# Light_Sensor.net
KiCad netlist of a schematic drawn in EAGLE
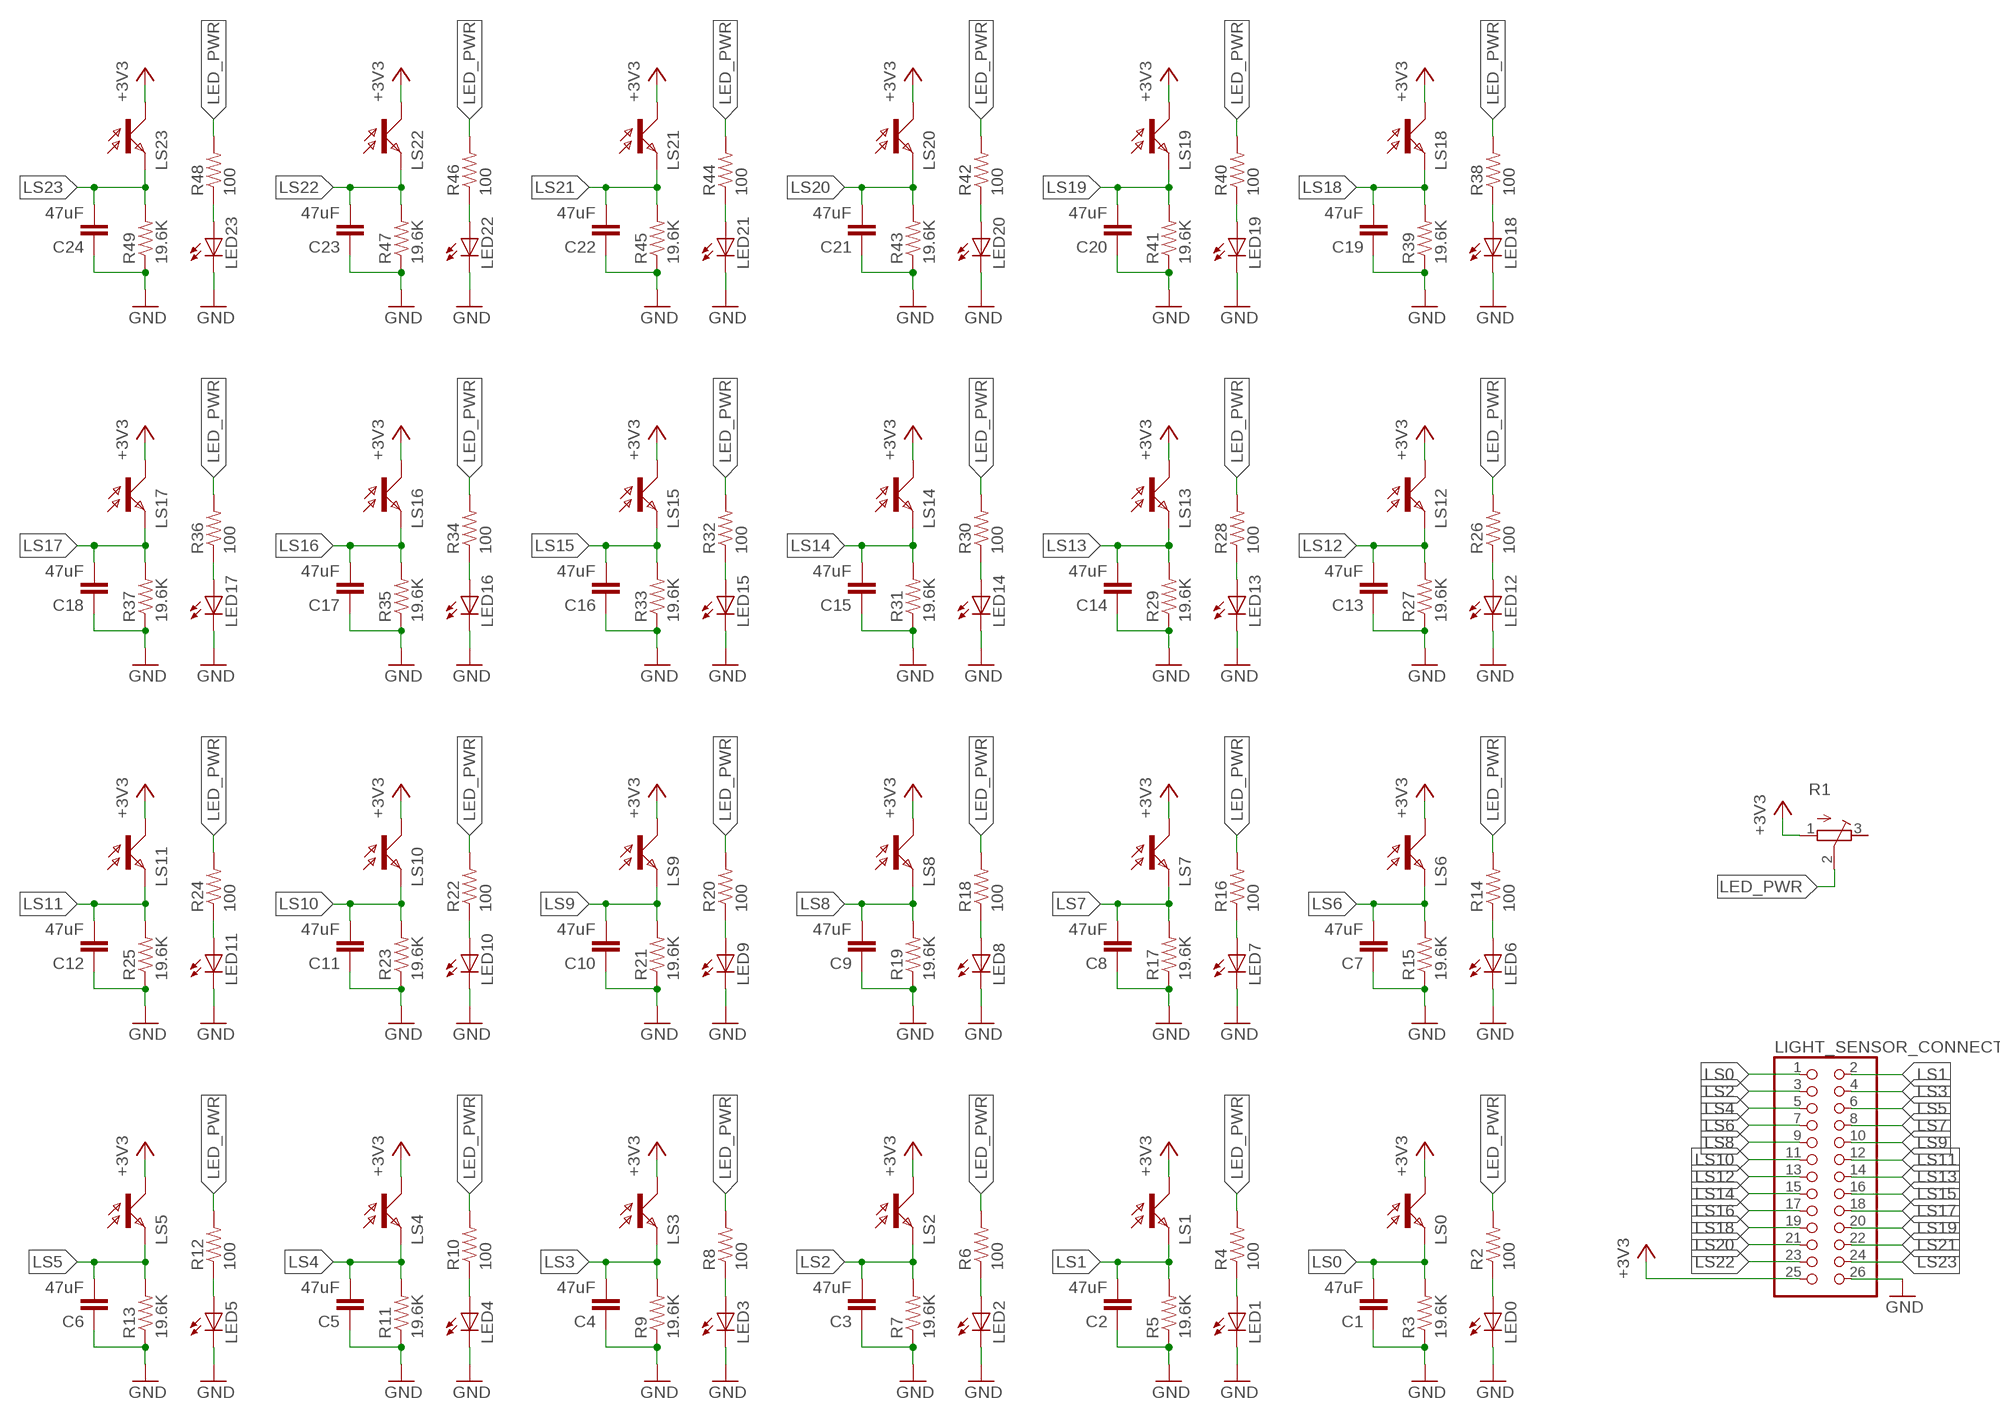
[diagram p0: schematic, sheet 1]

(export (version "E")
  (design (tool "Eeschema 10.0.6"))
  (components
    (comp (ref "C1")
      (value "47uF")
      (footprint "eagle-import:1206")
      (libsource (lib "eagle-import") (part "CAP1206"))
    )
    (comp (ref "C2")
      (value "47uF")
      (footprint "eagle-import:1206")
      (libsource (lib "eagle-import") (part "CAP1206"))
    )
    (comp (ref "C3")
      (value "47uF")
      (footprint "eagle-import:1206")
      (libsource (lib "eagle-import") (part "CAP1206"))
    )
    (comp (ref "C4")
      (value "47uF")
      (footprint "eagle-import:1206")
      (libsource (lib "eagle-import") (part "CAP1206"))
    )
    (comp (ref "C5")
      (value "47uF")
      (footprint "eagle-import:1206")
      (libsource (lib "eagle-import") (part "CAP1206"))
    )
    (comp (ref "C6")
      (value "47uF")
      (footprint "eagle-import:1206")
      (libsource (lib "eagle-import") (part "CAP1206"))
    )
    (comp (ref "C7")
      (value "47uF")
      (footprint "eagle-import:1206")
      (libsource (lib "eagle-import") (part "CAP1206"))
    )
    (comp (ref "C8")
      (value "47uF")
      (footprint "eagle-import:1206")
      (libsource (lib "eagle-import") (part "CAP1206"))
    )
    (comp (ref "C9")
      (value "47uF")
      (footprint "eagle-import:1206")
      (libsource (lib "eagle-import") (part "CAP1206"))
    )
    (comp (ref "C10")
      (value "47uF")
      (footprint "eagle-import:1206")
      (libsource (lib "eagle-import") (part "CAP1206"))
    )
    (comp (ref "C11")
      (value "47uF")
      (footprint "eagle-import:1206")
      (libsource (lib "eagle-import") (part "CAP1206"))
    )
    (comp (ref "C12")
      (value "47uF")
      (footprint "eagle-import:1206")
      (libsource (lib "eagle-import") (part "CAP1206"))
    )
    (comp (ref "C13")
      (value "47uF")
      (footprint "eagle-import:1206")
      (libsource (lib "eagle-import") (part "CAP1206"))
    )
    (comp (ref "C14")
      (value "47uF")
      (footprint "eagle-import:1206")
      (libsource (lib "eagle-import") (part "CAP1206"))
    )
    (comp (ref "C15")
      (value "47uF")
      (footprint "eagle-import:1206")
      (libsource (lib "eagle-import") (part "CAP1206"))
    )
    (comp (ref "C16")
      (value "47uF")
      (footprint "eagle-import:1206")
      (libsource (lib "eagle-import") (part "CAP1206"))
    )
    (comp (ref "C17")
      (value "47uF")
      (footprint "eagle-import:1206")
      (libsource (lib "eagle-import") (part "CAP1206"))
    )
    (comp (ref "C18")
      (value "47uF")
      (footprint "eagle-import:1206")
      (libsource (lib "eagle-import") (part "CAP1206"))
    )
    (comp (ref "C19")
      (value "47uF")
      (footprint "eagle-import:1206")
      (libsource (lib "eagle-import") (part "CAP1206"))
    )
    (comp (ref "C20")
      (value "47uF")
      (footprint "eagle-import:1206")
      (libsource (lib "eagle-import") (part "CAP1206"))
    )
    (comp (ref "C21")
      (value "47uF")
      (footprint "eagle-import:1206")
      (libsource (lib "eagle-import") (part "CAP1206"))
    )
    (comp (ref "C22")
      (value "47uF")
      (footprint "eagle-import:1206")
      (libsource (lib "eagle-import") (part "CAP1206"))
    )
    (comp (ref "C23")
      (value "47uF")
      (footprint "eagle-import:1206")
      (libsource (lib "eagle-import") (part "CAP1206"))
    )
    (comp (ref "C24")
      (value "47uF")
      (footprint "eagle-import:1206")
      (libsource (lib "eagle-import") (part "CAP1206"))
    )
    (comp (ref "LED0")
      (value "LEDCHIP-LED0603")
      (footprint "eagle-import:CHIP-LED0603")
      (libsource (lib "eagle-import") (part "LEDCHIP-LED0603"))
    )
    (comp (ref "LED1")
      (value "LEDCHIP-LED0603")
      (footprint "eagle-import:CHIP-LED0603")
      (libsource (lib "eagle-import") (part "LEDCHIP-LED0603"))
    )
    (comp (ref "LED2")
      (value "LEDCHIP-LED0603")
      (footprint "eagle-import:CHIP-LED0603")
      (libsource (lib "eagle-import") (part "LEDCHIP-LED0603"))
    )
    (comp (ref "LED3")
      (value "LEDCHIP-LED0603")
      (footprint "eagle-import:CHIP-LED0603")
      (libsource (lib "eagle-import") (part "LEDCHIP-LED0603"))
    )
    (comp (ref "LED4")
      (value "LEDCHIP-LED0603")
      (footprint "eagle-import:CHIP-LED0603")
      (libsource (lib "eagle-import") (part "LEDCHIP-LED0603"))
    )
    (comp (ref "LED5")
      (value "LEDCHIP-LED0603")
      (footprint "eagle-import:CHIP-LED0603")
      (libsource (lib "eagle-import") (part "LEDCHIP-LED0603"))
    )
    (comp (ref "LED6")
      (value "LEDCHIP-LED0603")
      (footprint "eagle-import:CHIP-LED0603")
      (libsource (lib "eagle-import") (part "LEDCHIP-LED0603"))
    )
    (comp (ref "LED7")
      (value "LEDCHIP-LED0603")
      (footprint "eagle-import:CHIP-LED0603")
      (libsource (lib "eagle-import") (part "LEDCHIP-LED0603"))
    )
    (comp (ref "LED8")
      (value "LEDCHIP-LED0603")
      (footprint "eagle-import:CHIP-LED0603")
      (libsource (lib "eagle-import") (part "LEDCHIP-LED0603"))
    )
    (comp (ref "LED9")
      (value "LEDCHIP-LED0603")
      (footprint "eagle-import:CHIP-LED0603")
      (libsource (lib "eagle-import") (part "LEDCHIP-LED0603"))
    )
    (comp (ref "LED10")
      (value "LEDCHIP-LED0603")
      (footprint "eagle-import:CHIP-LED0603")
      (libsource (lib "eagle-import") (part "LEDCHIP-LED0603"))
    )
    (comp (ref "LED11")
      (value "LEDCHIP-LED0603")
      (footprint "eagle-import:CHIP-LED0603")
      (libsource (lib "eagle-import") (part "LEDCHIP-LED0603"))
    )
    (comp (ref "LED12")
      (value "LEDCHIP-LED0603")
      (footprint "eagle-import:CHIP-LED0603")
      (libsource (lib "eagle-import") (part "LEDCHIP-LED0603"))
    )
    (comp (ref "LED13")
      (value "LEDCHIP-LED0603")
      (footprint "eagle-import:CHIP-LED0603")
      (libsource (lib "eagle-import") (part "LEDCHIP-LED0603"))
    )
    (comp (ref "LED14")
      (value "LEDCHIP-LED0603")
      (footprint "eagle-import:CHIP-LED0603")
      (libsource (lib "eagle-import") (part "LEDCHIP-LED0603"))
    )
    (comp (ref "LED15")
      (value "LEDCHIP-LED0603")
      (footprint "eagle-import:CHIP-LED0603")
      (libsource (lib "eagle-import") (part "LEDCHIP-LED0603"))
    )
    (comp (ref "LED16")
      (value "LEDCHIP-LED0603")
      (footprint "eagle-import:CHIP-LED0603")
      (libsource (lib "eagle-import") (part "LEDCHIP-LED0603"))
    )
    (comp (ref "LED17")
      (value "LEDCHIP-LED0603")
      (footprint "eagle-import:CHIP-LED0603")
      (libsource (lib "eagle-import") (part "LEDCHIP-LED0603"))
    )
    (comp (ref "LED18")
      (value "LEDCHIP-LED0603")
      (footprint "eagle-import:CHIP-LED0603")
      (libsource (lib "eagle-import") (part "LEDCHIP-LED0603"))
    )
    (comp (ref "LED19")
      (value "LEDCHIP-LED0603")
      (footprint "eagle-import:CHIP-LED0603")
      (libsource (lib "eagle-import") (part "LEDCHIP-LED0603"))
    )
    (comp (ref "LED20")
      (value "LEDCHIP-LED0603")
      (footprint "eagle-import:CHIP-LED0603")
      (libsource (lib "eagle-import") (part "LEDCHIP-LED0603"))
    )
    (comp (ref "LED21")
      (value "LEDCHIP-LED0603")
      (footprint "eagle-import:CHIP-LED0603")
      (libsource (lib "eagle-import") (part "LEDCHIP-LED0603"))
    )
    (comp (ref "LED22")
      (value "LEDCHIP-LED0603")
      (footprint "eagle-import:CHIP-LED0603")
      (libsource (lib "eagle-import") (part "LEDCHIP-LED0603"))
    )
    (comp (ref "LED23")
      (value "LEDCHIP-LED0603")
      (footprint "eagle-import:CHIP-LED0603")
      (libsource (lib "eagle-import") (part "LEDCHIP-LED0603"))
    )
    (comp (ref "LIGHT_SENSOR_CONNECTOR")
      (value "PINHD-2X13SMT")
      (footprint "eagle-import:2X13_SMT")
      (libsource (lib "eagle-import") (part "PINHD-2X13SMT"))
    )
    (comp (ref "LS0")
      (value "ALS")
      (footprint "eagle-import:SMD")
      (libsource (lib "eagle-import") (part "ALS"))
    )
    (comp (ref "LS1")
      (value "ALS")
      (footprint "eagle-import:SMD")
      (libsource (lib "eagle-import") (part "ALS"))
    )
    (comp (ref "LS2")
      (value "ALS")
      (footprint "eagle-import:SMD")
      (libsource (lib "eagle-import") (part "ALS"))
    )
    (comp (ref "LS3")
      (value "ALS")
      (footprint "eagle-import:SMD")
      (libsource (lib "eagle-import") (part "ALS"))
    )
    (comp (ref "LS4")
      (value "ALS")
      (footprint "eagle-import:SMD")
      (libsource (lib "eagle-import") (part "ALS"))
    )
    (comp (ref "LS5")
      (value "ALS")
      (footprint "eagle-import:SMD")
      (libsource (lib "eagle-import") (part "ALS"))
    )
    (comp (ref "LS6")
      (value "ALS")
      (footprint "eagle-import:SMD")
      (libsource (lib "eagle-import") (part "ALS"))
    )
    (comp (ref "LS7")
      (value "ALS")
      (footprint "eagle-import:SMD")
      (libsource (lib "eagle-import") (part "ALS"))
    )
    (comp (ref "LS8")
      (value "ALS")
      (footprint "eagle-import:SMD")
      (libsource (lib "eagle-import") (part "ALS"))
    )
    (comp (ref "LS9")
      (value "ALS")
      (footprint "eagle-import:SMD")
      (libsource (lib "eagle-import") (part "ALS"))
    )
    (comp (ref "LS10")
      (value "ALS")
      (footprint "eagle-import:SMD")
      (libsource (lib "eagle-import") (part "ALS"))
    )
    (comp (ref "LS11")
      (value "ALS")
      (footprint "eagle-import:SMD")
      (libsource (lib "eagle-import") (part "ALS"))
    )
    (comp (ref "LS12")
      (value "ALS")
      (footprint "eagle-import:SMD")
      (libsource (lib "eagle-import") (part "ALS"))
    )
    (comp (ref "LS13")
      (value "ALS")
      (footprint "eagle-import:SMD")
      (libsource (lib "eagle-import") (part "ALS"))
    )
    (comp (ref "LS14")
      (value "ALS")
      (footprint "eagle-import:SMD")
      (libsource (lib "eagle-import") (part "ALS"))
    )
    (comp (ref "LS15")
      (value "ALS")
      (footprint "eagle-import:SMD")
      (libsource (lib "eagle-import") (part "ALS"))
    )
    (comp (ref "LS16")
      (value "ALS")
      (footprint "eagle-import:SMD")
      (libsource (lib "eagle-import") (part "ALS"))
    )
    (comp (ref "LS17")
      (value "ALS")
      (footprint "eagle-import:SMD")
      (libsource (lib "eagle-import") (part "ALS"))
    )
    (comp (ref "LS18")
      (value "ALS")
      (footprint "eagle-import:SMD")
      (libsource (lib "eagle-import") (part "ALS"))
    )
    (comp (ref "LS19")
      (value "ALS")
      (footprint "eagle-import:SMD")
      (libsource (lib "eagle-import") (part "ALS"))
    )
    (comp (ref "LS20")
      (value "ALS")
      (footprint "eagle-import:SMD")
      (libsource (lib "eagle-import") (part "ALS"))
    )
    (comp (ref "LS21")
      (value "ALS")
      (footprint "eagle-import:SMD")
      (libsource (lib "eagle-import") (part "ALS"))
    )
    (comp (ref "LS22")
      (value "ALS")
      (footprint "eagle-import:SMD")
      (libsource (lib "eagle-import") (part "ALS"))
    )
    (comp (ref "LS23")
      (value "ALS")
      (footprint "eagle-import:SMD")
      (libsource (lib "eagle-import") (part "ALS"))
    )
    (comp (ref "R1")
      (value "R-TRIMM3296W")
      (footprint "eagle-import:RTRIM3296W")
      (libsource (lib "eagle-import") (part "R-TRIMM3296W"))
    )
    (comp (ref "R2")
      (value "100")
      (footprint "eagle-import:0603-RES")
      (libsource (lib "eagle-import") (part "RESISTOR0603"))
    )
    (comp (ref "R3")
      (value "19.6K")
      (footprint "eagle-import:0603-RES")
      (libsource (lib "eagle-import") (part "RESISTOR0603"))
    )
    (comp (ref "R4")
      (value "100")
      (footprint "eagle-import:0603-RES")
      (libsource (lib "eagle-import") (part "RESISTOR0603"))
    )
    (comp (ref "R5")
      (value "19.6K")
      (footprint "eagle-import:0603-RES")
      (libsource (lib "eagle-import") (part "RESISTOR0603"))
    )
    (comp (ref "R6")
      (value "100")
      (footprint "eagle-import:0603-RES")
      (libsource (lib "eagle-import") (part "RESISTOR0603"))
    )
    (comp (ref "R7")
      (value "19.6K")
      (footprint "eagle-import:0603-RES")
      (libsource (lib "eagle-import") (part "RESISTOR0603"))
    )
    (comp (ref "R8")
      (value "100")
      (footprint "eagle-import:0603-RES")
      (libsource (lib "eagle-import") (part "RESISTOR0603"))
    )
    (comp (ref "R9")
      (value "19.6K")
      (footprint "eagle-import:0603-RES")
      (libsource (lib "eagle-import") (part "RESISTOR0603"))
    )
    (comp (ref "R10")
      (value "100")
      (footprint "eagle-import:0603-RES")
      (libsource (lib "eagle-import") (part "RESISTOR0603"))
    )
    (comp (ref "R11")
      (value "19.6K")
      (footprint "eagle-import:0603-RES")
      (libsource (lib "eagle-import") (part "RESISTOR0603"))
    )
    (comp (ref "R12")
      (value "100")
      (footprint "eagle-import:0603-RES")
      (libsource (lib "eagle-import") (part "RESISTOR0603"))
    )
    (comp (ref "R13")
      (value "19.6K")
      (footprint "eagle-import:0603-RES")
      (libsource (lib "eagle-import") (part "RESISTOR0603"))
    )
    (comp (ref "R14")
      (value "100")
      (footprint "eagle-import:0603-RES")
      (libsource (lib "eagle-import") (part "RESISTOR0603"))
    )
    (comp (ref "R15")
      (value "19.6K")
      (footprint "eagle-import:0603-RES")
      (libsource (lib "eagle-import") (part "RESISTOR0603"))
    )
    (comp (ref "R16")
      (value "100")
      (footprint "eagle-import:0603-RES")
      (libsource (lib "eagle-import") (part "RESISTOR0603"))
    )
    (comp (ref "R17")
      (value "19.6K")
      (footprint "eagle-import:0603-RES")
      (libsource (lib "eagle-import") (part "RESISTOR0603"))
    )
    (comp (ref "R18")
      (value "100")
      (footprint "eagle-import:0603-RES")
      (libsource (lib "eagle-import") (part "RESISTOR0603"))
    )
    (comp (ref "R19")
      (value "19.6K")
      (footprint "eagle-import:0603-RES")
      (libsource (lib "eagle-import") (part "RESISTOR0603"))
    )
    (comp (ref "R20")
      (value "100")
      (footprint "eagle-import:0603-RES")
      (libsource (lib "eagle-import") (part "RESISTOR0603"))
    )
    (comp (ref "R21")
      (value "19.6K")
      (footprint "eagle-import:0603-RES")
      (libsource (lib "eagle-import") (part "RESISTOR0603"))
    )
    (comp (ref "R22")
      (value "100")
      (footprint "eagle-import:0603-RES")
      (libsource (lib "eagle-import") (part "RESISTOR0603"))
    )
    (comp (ref "R23")
      (value "19.6K")
      (footprint "eagle-import:0603-RES")
      (libsource (lib "eagle-import") (part "RESISTOR0603"))
    )
    (comp (ref "R24")
      (value "100")
      (footprint "eagle-import:0603-RES")
      (libsource (lib "eagle-import") (part "RESISTOR0603"))
    )
    (comp (ref "R25")
      (value "19.6K")
      (footprint "eagle-import:0603-RES")
      (libsource (lib "eagle-import") (part "RESISTOR0603"))
    )
    (comp (ref "R26")
      (value "100")
      (footprint "eagle-import:0603-RES")
      (libsource (lib "eagle-import") (part "RESISTOR0603"))
    )
    (comp (ref "R27")
      (value "19.6K")
      (footprint "eagle-import:0603-RES")
      (libsource (lib "eagle-import") (part "RESISTOR0603"))
    )
    (comp (ref "R28")
      (value "100")
      (footprint "eagle-import:0603-RES")
      (libsource (lib "eagle-import") (part "RESISTOR0603"))
    )
    (comp (ref "R29")
      (value "19.6K")
      (footprint "eagle-import:0603-RES")
      (libsource (lib "eagle-import") (part "RESISTOR0603"))
    )
    (comp (ref "R30")
      (value "100")
      (footprint "eagle-import:0603-RES")
      (libsource (lib "eagle-import") (part "RESISTOR0603"))
    )
    (comp (ref "R31")
      (value "19.6K")
      (footprint "eagle-import:0603-RES")
      (libsource (lib "eagle-import") (part "RESISTOR0603"))
    )
    (comp (ref "R32")
      (value "100")
      (footprint "eagle-import:0603-RES")
      (libsource (lib "eagle-import") (part "RESISTOR0603"))
    )
    (comp (ref "R33")
      (value "19.6K")
      (footprint "eagle-import:0603-RES")
      (libsource (lib "eagle-import") (part "RESISTOR0603"))
    )
    (comp (ref "R34")
      (value "100")
      (footprint "eagle-import:0603-RES")
      (libsource (lib "eagle-import") (part "RESISTOR0603"))
    )
    (comp (ref "R35")
      (value "19.6K")
      (footprint "eagle-import:0603-RES")
      (libsource (lib "eagle-import") (part "RESISTOR0603"))
    )
    (comp (ref "R36")
      (value "100")
      (footprint "eagle-import:0603-RES")
      (libsource (lib "eagle-import") (part "RESISTOR0603"))
    )
    (comp (ref "R37")
      (value "19.6K")
      (footprint "eagle-import:0603-RES")
      (libsource (lib "eagle-import") (part "RESISTOR0603"))
    )
    (comp (ref "R38")
      (value "100")
      (footprint "eagle-import:0603-RES")
      (libsource (lib "eagle-import") (part "RESISTOR0603"))
    )
    (comp (ref "R39")
      (value "19.6K")
      (footprint "eagle-import:0603-RES")
      (libsource (lib "eagle-import") (part "RESISTOR0603"))
    )
    (comp (ref "R40")
      (value "100")
      (footprint "eagle-import:0603-RES")
      (libsource (lib "eagle-import") (part "RESISTOR0603"))
    )
    (comp (ref "R41")
      (value "19.6K")
      (footprint "eagle-import:0603-RES")
      (libsource (lib "eagle-import") (part "RESISTOR0603"))
    )
    (comp (ref "R42")
      (value "100")
      (footprint "eagle-import:0603-RES")
      (libsource (lib "eagle-import") (part "RESISTOR0603"))
    )
    (comp (ref "R43")
      (value "19.6K")
      (footprint "eagle-import:0603-RES")
      (libsource (lib "eagle-import") (part "RESISTOR0603"))
    )
    (comp (ref "R44")
      (value "100")
      (footprint "eagle-import:0603-RES")
      (libsource (lib "eagle-import") (part "RESISTOR0603"))
    )
    (comp (ref "R45")
      (value "19.6K")
      (footprint "eagle-import:0603-RES")
      (libsource (lib "eagle-import") (part "RESISTOR0603"))
    )
    (comp (ref "R46")
      (value "100")
      (footprint "eagle-import:0603-RES")
      (libsource (lib "eagle-import") (part "RESISTOR0603"))
    )
    (comp (ref "R47")
      (value "19.6K")
      (footprint "eagle-import:0603-RES")
      (libsource (lib "eagle-import") (part "RESISTOR0603"))
    )
    (comp (ref "R48")
      (value "100")
      (footprint "eagle-import:0603-RES")
      (libsource (lib "eagle-import") (part "RESISTOR0603"))
    )
    (comp (ref "R49")
      (value "19.6K")
      (footprint "eagle-import:0603-RES")
      (libsource (lib "eagle-import") (part "RESISTOR0603"))
    )
  )
  (nets
    (net (code "1") (name "+3V3") (class "Default")
      (node (ref "LIGHT_SENSOR_CONNECTOR") (pin "25") (pinfunction "25_25") (pintype "passive"))
      (node (ref "LS0") (pin "C") (pinfunction "C_C") (pintype "passive"))
      (node (ref "LS1") (pin "C") (pinfunction "C_C") (pintype "passive"))
      (node (ref "LS10") (pin "C") (pinfunction "C_C") (pintype "passive"))
      (node (ref "LS11") (pin "C") (pinfunction "C_C") (pintype "passive"))
      (node (ref "LS12") (pin "C") (pinfunction "C_C") (pintype "passive"))
      (node (ref "LS13") (pin "C") (pinfunction "C_C") (pintype "passive"))
      (node (ref "LS14") (pin "C") (pinfunction "C_C") (pintype "passive"))
      (node (ref "LS15") (pin "C") (pinfunction "C_C") (pintype "passive"))
      (node (ref "LS16") (pin "C") (pinfunction "C_C") (pintype "passive"))
      (node (ref "LS17") (pin "C") (pinfunction "C_C") (pintype "passive"))
      (node (ref "LS18") (pin "C") (pinfunction "C_C") (pintype "passive"))
      (node (ref "LS19") (pin "C") (pinfunction "C_C") (pintype "passive"))
      (node (ref "LS2") (pin "C") (pinfunction "C_C") (pintype "passive"))
      (node (ref "LS20") (pin "C") (pinfunction "C_C") (pintype "passive"))
      (node (ref "LS21") (pin "C") (pinfunction "C_C") (pintype "passive"))
      (node (ref "LS22") (pin "C") (pinfunction "C_C") (pintype "passive"))
      (node (ref "LS23") (pin "C") (pinfunction "C_C") (pintype "passive"))
      (node (ref "LS3") (pin "C") (pinfunction "C_C") (pintype "passive"))
      (node (ref "LS4") (pin "C") (pinfunction "C_C") (pintype "passive"))
      (node (ref "LS5") (pin "C") (pinfunction "C_C") (pintype "passive"))
      (node (ref "LS6") (pin "C") (pinfunction "C_C") (pintype "passive"))
      (node (ref "LS7") (pin "C") (pinfunction "C_C") (pintype "passive"))
      (node (ref "LS8") (pin "C") (pinfunction "C_C") (pintype "passive"))
      (node (ref "LS9") (pin "C") (pinfunction "C_C") (pintype "passive"))
      (node (ref "R1") (pin "1") (pinfunction "A_1") (pintype "passive"))
    )
    (net (code "2") (name "GND") (class "Default")
      (node (ref "C1") (pin "1") (pinfunction "1_1") (pintype "passive"))
      (node (ref "C10") (pin "1") (pinfunction "1_1") (pintype "passive"))
      (node (ref "C11") (pin "1") (pinfunction "1_1") (pintype "passive"))
      (node (ref "C12") (pin "1") (pinfunction "1_1") (pintype "passive"))
      (node (ref "C13") (pin "1") (pinfunction "1_1") (pintype "passive"))
      (node (ref "C14") (pin "1") (pinfunction "1_1") (pintype "passive"))
      (node (ref "C15") (pin "1") (pinfunction "1_1") (pintype "passive"))
      (node (ref "C16") (pin "1") (pinfunction "1_1") (pintype "passive"))
      (node (ref "C17") (pin "1") (pinfunction "1_1") (pintype "passive"))
      (node (ref "C18") (pin "1") (pinfunction "1_1") (pintype "passive"))
      (node (ref "C19") (pin "1") (pinfunction "1_1") (pintype "passive"))
      (node (ref "C2") (pin "1") (pinfunction "1_1") (pintype "passive"))
      (node (ref "C20") (pin "1") (pinfunction "1_1") (pintype "passive"))
      (node (ref "C21") (pin "1") (pinfunction "1_1") (pintype "passive"))
      (node (ref "C22") (pin "1") (pinfunction "1_1") (pintype "passive"))
      (node (ref "C23") (pin "1") (pinfunction "1_1") (pintype "passive"))
      (node (ref "C24") (pin "1") (pinfunction "1_1") (pintype "passive"))
      (node (ref "C3") (pin "1") (pinfunction "1_1") (pintype "passive"))
      (node (ref "C4") (pin "1") (pinfunction "1_1") (pintype "passive"))
      (node (ref "C5") (pin "1") (pinfunction "1_1") (pintype "passive"))
      (node (ref "C6") (pin "1") (pinfunction "1_1") (pintype "passive"))
      (node (ref "C7") (pin "1") (pinfunction "1_1") (pintype "passive"))
      (node (ref "C8") (pin "1") (pinfunction "1_1") (pintype "passive"))
      (node (ref "C9") (pin "1") (pinfunction "1_1") (pintype "passive"))
      (node (ref "LED0") (pin "C") (pinfunction "C_C") (pintype "passive"))
      (node (ref "LED1") (pin "C") (pinfunction "C_C") (pintype "passive"))
      (node (ref "LED10") (pin "C") (pinfunction "C_C") (pintype "passive"))
      (node (ref "LED11") (pin "C") (pinfunction "C_C") (pintype "passive"))
      (node (ref "LED12") (pin "C") (pinfunction "C_C") (pintype "passive"))
      (node (ref "LED13") (pin "C") (pinfunction "C_C") (pintype "passive"))
      (node (ref "LED14") (pin "C") (pinfunction "C_C") (pintype "passive"))
      (node (ref "LED15") (pin "C") (pinfunction "C_C") (pintype "passive"))
      (node (ref "LED16") (pin "C") (pinfunction "C_C") (pintype "passive"))
      (node (ref "LED17") (pin "C") (pinfunction "C_C") (pintype "passive"))
      (node (ref "LED18") (pin "C") (pinfunction "C_C") (pintype "passive"))
      (node (ref "LED19") (pin "C") (pinfunction "C_C") (pintype "passive"))
      (node (ref "LED2") (pin "C") (pinfunction "C_C") (pintype "passive"))
      (node (ref "LED20") (pin "C") (pinfunction "C_C") (pintype "passive"))
      (node (ref "LED21") (pin "C") (pinfunction "C_C") (pintype "passive"))
      (node (ref "LED22") (pin "C") (pinfunction "C_C") (pintype "passive"))
      (node (ref "LED23") (pin "C") (pinfunction "C_C") (pintype "passive"))
      (node (ref "LED3") (pin "C") (pinfunction "C_C") (pintype "passive"))
      (node (ref "LED4") (pin "C") (pinfunction "C_C") (pintype "passive"))
      (node (ref "LED5") (pin "C") (pinfunction "C_C") (pintype "passive"))
      (node (ref "LED6") (pin "C") (pinfunction "C_C") (pintype "passive"))
      (node (ref "LED7") (pin "C") (pinfunction "C_C") (pintype "passive"))
      (node (ref "LED8") (pin "C") (pinfunction "C_C") (pintype "passive"))
      (node (ref "LED9") (pin "C") (pinfunction "C_C") (pintype "passive"))
      (node (ref "LIGHT_SENSOR_CONNECTOR") (pin "26") (pinfunction "26_26") (pintype "passive"))
      (node (ref "R11") (pin "1") (pinfunction "1_1") (pintype "passive"))
      (node (ref "R13") (pin "1") (pinfunction "1_1") (pintype "passive"))
      (node (ref "R15") (pin "1") (pinfunction "1_1") (pintype "passive"))
      (node (ref "R17") (pin "1") (pinfunction "1_1") (pintype "passive"))
      (node (ref "R19") (pin "1") (pinfunction "1_1") (pintype "passive"))
      (node (ref "R21") (pin "1") (pinfunction "1_1") (pintype "passive"))
      (node (ref "R23") (pin "1") (pinfunction "1_1") (pintype "passive"))
      (node (ref "R25") (pin "1") (pinfunction "1_1") (pintype "passive"))
      (node (ref "R27") (pin "1") (pinfunction "1_1") (pintype "passive"))
      (node (ref "R29") (pin "1") (pinfunction "1_1") (pintype "passive"))
      (node (ref "R3") (pin "1") (pinfunction "1_1") (pintype "passive"))
      (node (ref "R31") (pin "1") (pinfunction "1_1") (pintype "passive"))
      (node (ref "R33") (pin "1") (pinfunction "1_1") (pintype "passive"))
      (node (ref "R35") (pin "1") (pinfunction "1_1") (pintype "passive"))
      (node (ref "R37") (pin "1") (pinfunction "1_1") (pintype "passive"))
      (node (ref "R39") (pin "1") (pinfunction "1_1") (pintype "passive"))
      (node (ref "R41") (pin "1") (pinfunction "1_1") (pintype "passive"))
      (node (ref "R43") (pin "1") (pinfunction "1_1") (pintype "passive"))
      (node (ref "R45") (pin "1") (pinfunction "1_1") (pintype "passive"))
      (node (ref "R47") (pin "1") (pinfunction "1_1") (pintype "passive"))
      (node (ref "R49") (pin "1") (pinfunction "1_1") (pintype "passive"))
      (node (ref "R5") (pin "1") (pinfunction "1_1") (pintype "passive"))
      (node (ref "R7") (pin "1") (pinfunction "1_1") (pintype "passive"))
      (node (ref "R9") (pin "1") (pinfunction "1_1") (pintype "passive"))
    )
    (net (code "3") (name "LED_PWR") (class "Default")
      (node (ref "R1") (pin "2") (pinfunction "S_2") (pintype "passive"))
      (node (ref "R10") (pin "2") (pinfunction "2_2") (pintype "passive"))
      (node (ref "R12") (pin "2") (pinfunction "2_2") (pintype "passive"))
      (node (ref "R14") (pin "2") (pinfunction "2_2") (pintype "passive"))
      (node (ref "R16") (pin "2") (pinfunction "2_2") (pintype "passive"))
      (node (ref "R18") (pin "2") (pinfunction "2_2") (pintype "passive"))
      (node (ref "R2") (pin "2") (pinfunction "2_2") (pintype "passive"))
      (node (ref "R20") (pin "2") (pinfunction "2_2") (pintype "passive"))
      (node (ref "R22") (pin "2") (pinfunction "2_2") (pintype "passive"))
      (node (ref "R24") (pin "2") (pinfunction "2_2") (pintype "passive"))
      (node (ref "R26") (pin "2") (pinfunction "2_2") (pintype "passive"))
      (node (ref "R28") (pin "2") (pinfunction "2_2") (pintype "passive"))
      (node (ref "R30") (pin "2") (pinfunction "2_2") (pintype "passive"))
      (node (ref "R32") (pin "2") (pinfunction "2_2") (pintype "passive"))
      (node (ref "R34") (pin "2") (pinfunction "2_2") (pintype "passive"))
      (node (ref "R36") (pin "2") (pinfunction "2_2") (pintype "passive"))
      (node (ref "R38") (pin "2") (pinfunction "2_2") (pintype "passive"))
      (node (ref "R4") (pin "2") (pinfunction "2_2") (pintype "passive"))
      (node (ref "R40") (pin "2") (pinfunction "2_2") (pintype "passive"))
      (node (ref "R42") (pin "2") (pinfunction "2_2") (pintype "passive"))
      (node (ref "R44") (pin "2") (pinfunction "2_2") (pintype "passive"))
      (node (ref "R46") (pin "2") (pinfunction "2_2") (pintype "passive"))
      (node (ref "R48") (pin "2") (pinfunction "2_2") (pintype "passive"))
      (node (ref "R6") (pin "2") (pinfunction "2_2") (pintype "passive"))
      (node (ref "R8") (pin "2") (pinfunction "2_2") (pintype "passive"))
    )
    (net (code "4") (name "LS0") (class "Default")
      (node (ref "C1") (pin "2") (pinfunction "2_2") (pintype "passive"))
      (node (ref "LIGHT_SENSOR_CONNECTOR") (pin "1") (pinfunction "1_1") (pintype "passive"))
      (node (ref "LS0") (pin "E") (pinfunction "E_E") (pintype "passive"))
      (node (ref "R3") (pin "2") (pinfunction "2_2") (pintype "passive"))
    )
    (net (code "5") (name "LS1") (class "Default")
      (node (ref "C2") (pin "2") (pinfunction "2_2") (pintype "passive"))
      (node (ref "LIGHT_SENSOR_CONNECTOR") (pin "2") (pinfunction "2_2") (pintype "passive"))
      (node (ref "LS1") (pin "E") (pinfunction "E_E") (pintype "passive"))
      (node (ref "R5") (pin "2") (pinfunction "2_2") (pintype "passive"))
    )
    (net (code "6") (name "LS2") (class "Default")
      (node (ref "C3") (pin "2") (pinfunction "2_2") (pintype "passive"))
      (node (ref "LIGHT_SENSOR_CONNECTOR") (pin "3") (pinfunction "3_3") (pintype "passive"))
      (node (ref "LS2") (pin "E") (pinfunction "E_E") (pintype "passive"))
      (node (ref "R7") (pin "2") (pinfunction "2_2") (pintype "passive"))
    )
    (net (code "7") (name "LS3") (class "Default")
      (node (ref "C4") (pin "2") (pinfunction "2_2") (pintype "passive"))
      (node (ref "LIGHT_SENSOR_CONNECTOR") (pin "4") (pinfunction "4_4") (pintype "passive"))
      (node (ref "LS3") (pin "E") (pinfunction "E_E") (pintype "passive"))
      (node (ref "R9") (pin "2") (pinfunction "2_2") (pintype "passive"))
    )
    (net (code "8") (name "LS4") (class "Default")
      (node (ref "C5") (pin "2") (pinfunction "2_2") (pintype "passive"))
      (node (ref "LIGHT_SENSOR_CONNECTOR") (pin "5") (pinfunction "5_5") (pintype "passive"))
      (node (ref "LS4") (pin "E") (pinfunction "E_E") (pintype "passive"))
      (node (ref "R11") (pin "2") (pinfunction "2_2") (pintype "passive"))
    )
    (net (code "9") (name "LS5") (class "Default")
      (node (ref "C6") (pin "2") (pinfunction "2_2") (pintype "passive"))
      (node (ref "LIGHT_SENSOR_CONNECTOR") (pin "6") (pinfunction "6_6") (pintype "passive"))
      (node (ref "LS5") (pin "E") (pinfunction "E_E") (pintype "passive"))
      (node (ref "R13") (pin "2") (pinfunction "2_2") (pintype "passive"))
    )
    (net (code "10") (name "LS6") (class "Default")
      (node (ref "C7") (pin "2") (pinfunction "2_2") (pintype "passive"))
      (node (ref "LIGHT_SENSOR_CONNECTOR") (pin "7") (pinfunction "7_7") (pintype "passive"))
      (node (ref "LS6") (pin "E") (pinfunction "E_E") (pintype "passive"))
      (node (ref "R15") (pin "2") (pinfunction "2_2") (pintype "passive"))
    )
    (net (code "11") (name "LS7") (class "Default")
      (node (ref "C8") (pin "2") (pinfunction "2_2") (pintype "passive"))
      (node (ref "LIGHT_SENSOR_CONNECTOR") (pin "8") (pinfunction "8_8") (pintype "passive"))
      (node (ref "LS7") (pin "E") (pinfunction "E_E") (pintype "passive"))
      (node (ref "R17") (pin "2") (pinfunction "2_2") (pintype "passive"))
    )
    (net (code "12") (name "LS8") (class "Default")
      (node (ref "C9") (pin "2") (pinfunction "2_2") (pintype "passive"))
      (node (ref "LIGHT_SENSOR_CONNECTOR") (pin "9") (pinfunction "9_9") (pintype "passive"))
      (node (ref "LS8") (pin "E") (pinfunction "E_E") (pintype "passive"))
      (node (ref "R19") (pin "2") (pinfunction "2_2") (pintype "passive"))
    )
    (net (code "13") (name "LS9") (class "Default")
      (node (ref "C10") (pin "2") (pinfunction "2_2") (pintype "passive"))
      (node (ref "LIGHT_SENSOR_CONNECTOR") (pin "10") (pinfunction "10_10") (pintype "passive"))
      (node (ref "LS9") (pin "E") (pinfunction "E_E") (pintype "passive"))
      (node (ref "R21") (pin "2") (pinfunction "2_2") (pintype "passive"))
    )
    (net (code "14") (name "LS10") (class "Default")
      (node (ref "C11") (pin "2") (pinfunction "2_2") (pintype "passive"))
      (node (ref "LIGHT_SENSOR_CONNECTOR") (pin "11") (pinfunction "11_11") (pintype "passive"))
      (node (ref "LS10") (pin "E") (pinfunction "E_E") (pintype "passive"))
      (node (ref "R23") (pin "2") (pinfunction "2_2") (pintype "passive"))
    )
    (net (code "15") (name "LS11") (class "Default")
      (node (ref "C12") (pin "2") (pinfunction "2_2") (pintype "passive"))
      (node (ref "LIGHT_SENSOR_CONNECTOR") (pin "12") (pinfunction "12_12") (pintype "passive"))
      (node (ref "LS11") (pin "E") (pinfunction "E_E") (pintype "passive"))
      (node (ref "R25") (pin "2") (pinfunction "2_2") (pintype "passive"))
    )
    (net (code "16") (name "LS12") (class "Default")
      (node (ref "C13") (pin "2") (pinfunction "2_2") (pintype "passive"))
      (node (ref "LIGHT_SENSOR_CONNECTOR") (pin "13") (pinfunction "13_13") (pintype "passive"))
      (node (ref "LS12") (pin "E") (pinfunction "E_E") (pintype "passive"))
      (node (ref "R27") (pin "2") (pinfunction "2_2") (pintype "passive"))
    )
    (net (code "17") (name "LS13") (class "Default")
      (node (ref "C14") (pin "2") (pinfunction "2_2") (pintype "passive"))
      (node (ref "LIGHT_SENSOR_CONNECTOR") (pin "14") (pinfunction "14_14") (pintype "passive"))
      (node (ref "LS13") (pin "E") (pinfunction "E_E") (pintype "passive"))
      (node (ref "R29") (pin "2") (pinfunction "2_2") (pintype "passive"))
    )
    (net (code "18") (name "LS14") (class "Default")
      (node (ref "C15") (pin "2") (pinfunction "2_2") (pintype "passive"))
      (node (ref "LIGHT_SENSOR_CONNECTOR") (pin "15") (pinfunction "15_15") (pintype "passive"))
      (node (ref "LS14") (pin "E") (pinfunction "E_E") (pintype "passive"))
      (node (ref "R31") (pin "2") (pinfunction "2_2") (pintype "passive"))
    )
    (net (code "19") (name "LS15") (class "Default")
      (node (ref "C16") (pin "2") (pinfunction "2_2") (pintype "passive"))
      (node (ref "LIGHT_SENSOR_CONNECTOR") (pin "16") (pinfunction "16_16") (pintype "passive"))
      (node (ref "LS15") (pin "E") (pinfunction "E_E") (pintype "passive"))
      (node (ref "R33") (pin "2") (pinfunction "2_2") (pintype "passive"))
    )
    (net (code "20") (name "LS16") (class "Default")
      (node (ref "C17") (pin "2") (pinfunction "2_2") (pintype "passive"))
      (node (ref "LIGHT_SENSOR_CONNECTOR") (pin "17") (pinfunction "17_17") (pintype "passive"))
      (node (ref "LS16") (pin "E") (pinfunction "E_E") (pintype "passive"))
      (node (ref "R35") (pin "2") (pinfunction "2_2") (pintype "passive"))
    )
    (net (code "21") (name "LS17") (class "Default")
      (node (ref "C18") (pin "2") (pinfunction "2_2") (pintype "passive"))
      (node (ref "LIGHT_SENSOR_CONNECTOR") (pin "18") (pinfunction "18_18") (pintype "passive"))
      (node (ref "LS17") (pin "E") (pinfunction "E_E") (pintype "passive"))
      (node (ref "R37") (pin "2") (pinfunction "2_2") (pintype "passive"))
    )
    (net (code "22") (name "LS18") (class "Default")
      (node (ref "C19") (pin "2") (pinfunction "2_2") (pintype "passive"))
      (node (ref "LIGHT_SENSOR_CONNECTOR") (pin "19") (pinfunction "19_19") (pintype "passive"))
      (node (ref "LS18") (pin "E") (pinfunction "E_E") (pintype "passive"))
      (node (ref "R39") (pin "2") (pinfunction "2_2") (pintype "passive"))
    )
    (net (code "23") (name "LS19") (class "Default")
      (node (ref "C20") (pin "2") (pinfunction "2_2") (pintype "passive"))
      (node (ref "LIGHT_SENSOR_CONNECTOR") (pin "20") (pinfunction "20_20") (pintype "passive"))
      (node (ref "LS19") (pin "E") (pinfunction "E_E") (pintype "passive"))
      (node (ref "R41") (pin "2") (pinfunction "2_2") (pintype "passive"))
    )
    (net (code "24") (name "LS20") (class "Default")
      (node (ref "C21") (pin "2") (pinfunction "2_2") (pintype "passive"))
      (node (ref "LIGHT_SENSOR_CONNECTOR") (pin "21") (pinfunction "21_21") (pintype "passive"))
      (node (ref "LS20") (pin "E") (pinfunction "E_E") (pintype "passive"))
      (node (ref "R43") (pin "2") (pinfunction "2_2") (pintype "passive"))
    )
    (net (code "25") (name "LS21") (class "Default")
      (node (ref "C22") (pin "2") (pinfunction "2_2") (pintype "passive"))
      (node (ref "LIGHT_SENSOR_CONNECTOR") (pin "22") (pinfunction "22_22") (pintype "passive"))
      (node (ref "LS21") (pin "E") (pinfunction "E_E") (pintype "passive"))
      (node (ref "R45") (pin "2") (pinfunction "2_2") (pintype "passive"))
    )
    (net (code "26") (name "LS22") (class "Default")
      (node (ref "C23") (pin "2") (pinfunction "2_2") (pintype "passive"))
      (node (ref "LIGHT_SENSOR_CONNECTOR") (pin "23") (pinfunction "23_23") (pintype "passive"))
      (node (ref "LS22") (pin "E") (pinfunction "E_E") (pintype "passive"))
      (node (ref "R47") (pin "2") (pinfunction "2_2") (pintype "passive"))
    )
    (net (code "27") (name "LS23") (class "Default")
      (node (ref "C24") (pin "2") (pinfunction "2_2") (pintype "passive"))
      (node (ref "LIGHT_SENSOR_CONNECTOR") (pin "24") (pinfunction "24_24") (pintype "passive"))
      (node (ref "LS23") (pin "E") (pinfunction "E_E") (pintype "passive"))
      (node (ref "R49") (pin "2") (pinfunction "2_2") (pintype "passive"))
    )
    (net (code "28") (name "Net-(LED0-PadA)") (class "Default")
      (node (ref "LED0") (pin "A") (pinfunction "A_A") (pintype "passive"))
      (node (ref "R2") (pin "1") (pinfunction "1_1") (pintype "passive"))
    )
    (net (code "29") (name "Net-(LED1-PadA)") (class "Default")
      (node (ref "LED1") (pin "A") (pinfunction "A_A") (pintype "passive"))
      (node (ref "R4") (pin "1") (pinfunction "1_1") (pintype "passive"))
    )
    (net (code "30") (name "Net-(LED2-PadA)") (class "Default")
      (node (ref "LED2") (pin "A") (pinfunction "A_A") (pintype "passive"))
      (node (ref "R6") (pin "1") (pinfunction "1_1") (pintype "passive"))
    )
    (net (code "31") (name "Net-(LED3-PadA)") (class "Default")
      (node (ref "LED3") (pin "A") (pinfunction "A_A") (pintype "passive"))
      (node (ref "R8") (pin "1") (pinfunction "1_1") (pintype "passive"))
    )
    (net (code "32") (name "Net-(LED4-PadA)") (class "Default")
      (node (ref "LED4") (pin "A") (pinfunction "A_A") (pintype "passive"))
      (node (ref "R10") (pin "1") (pinfunction "1_1") (pintype "passive"))
    )
    (net (code "33") (name "Net-(LED5-PadA)") (class "Default")
      (node (ref "LED5") (pin "A") (pinfunction "A_A") (pintype "passive"))
      (node (ref "R12") (pin "1") (pinfunction "1_1") (pintype "passive"))
    )
    (net (code "34") (name "Net-(LED6-PadA)") (class "Default")
      (node (ref "LED6") (pin "A") (pinfunction "A_A") (pintype "passive"))
      (node (ref "R14") (pin "1") (pinfunction "1_1") (pintype "passive"))
    )
    (net (code "35") (name "Net-(LED7-PadA)") (class "Default")
      (node (ref "LED7") (pin "A") (pinfunction "A_A") (pintype "passive"))
      (node (ref "R16") (pin "1") (pinfunction "1_1") (pintype "passive"))
    )
    (net (code "36") (name "Net-(LED8-PadA)") (class "Default")
      (node (ref "LED8") (pin "A") (pinfunction "A_A") (pintype "passive"))
      (node (ref "R18") (pin "1") (pinfunction "1_1") (pintype "passive"))
    )
    (net (code "37") (name "Net-(LED9-PadA)") (class "Default")
      (node (ref "LED9") (pin "A") (pinfunction "A_A") (pintype "passive"))
      (node (ref "R20") (pin "1") (pinfunction "1_1") (pintype "passive"))
    )
    (net (code "38") (name "Net-(LED10-PadA)") (class "Default")
      (node (ref "LED10") (pin "A") (pinfunction "A_A") (pintype "passive"))
      (node (ref "R22") (pin "1") (pinfunction "1_1") (pintype "passive"))
    )
    (net (code "39") (name "Net-(LED11-PadA)") (class "Default")
      (node (ref "LED11") (pin "A") (pinfunction "A_A") (pintype "passive"))
      (node (ref "R24") (pin "1") (pinfunction "1_1") (pintype "passive"))
    )
    (net (code "40") (name "Net-(LED12-PadA)") (class "Default")
      (node (ref "LED12") (pin "A") (pinfunction "A_A") (pintype "passive"))
      (node (ref "R26") (pin "1") (pinfunction "1_1") (pintype "passive"))
    )
    (net (code "41") (name "Net-(LED13-PadA)") (class "Default")
      (node (ref "LED13") (pin "A") (pinfunction "A_A") (pintype "passive"))
      (node (ref "R28") (pin "1") (pinfunction "1_1") (pintype "passive"))
    )
    (net (code "42") (name "Net-(LED14-PadA)") (class "Default")
      (node (ref "LED14") (pin "A") (pinfunction "A_A") (pintype "passive"))
      (node (ref "R30") (pin "1") (pinfunction "1_1") (pintype "passive"))
    )
    (net (code "43") (name "Net-(LED15-PadA)") (class "Default")
      (node (ref "LED15") (pin "A") (pinfunction "A_A") (pintype "passive"))
      (node (ref "R32") (pin "1") (pinfunction "1_1") (pintype "passive"))
    )
    (net (code "44") (name "Net-(LED16-PadA)") (class "Default")
      (node (ref "LED16") (pin "A") (pinfunction "A_A") (pintype "passive"))
      (node (ref "R34") (pin "1") (pinfunction "1_1") (pintype "passive"))
    )
    (net (code "45") (name "Net-(LED17-PadA)") (class "Default")
      (node (ref "LED17") (pin "A") (pinfunction "A_A") (pintype "passive"))
      (node (ref "R36") (pin "1") (pinfunction "1_1") (pintype "passive"))
    )
    (net (code "46") (name "Net-(LED18-PadA)") (class "Default")
      (node (ref "LED18") (pin "A") (pinfunction "A_A") (pintype "passive"))
      (node (ref "R38") (pin "1") (pinfunction "1_1") (pintype "passive"))
    )
    (net (code "47") (name "Net-(LED19-PadA)") (class "Default")
      (node (ref "LED19") (pin "A") (pinfunction "A_A") (pintype "passive"))
      (node (ref "R40") (pin "1") (pinfunction "1_1") (pintype "passive"))
    )
    (net (code "48") (name "Net-(LED20-PadA)") (class "Default")
      (node (ref "LED20") (pin "A") (pinfunction "A_A") (pintype "passive"))
      (node (ref "R42") (pin "1") (pinfunction "1_1") (pintype "passive"))
    )
    (net (code "49") (name "Net-(LED21-PadA)") (class "Default")
      (node (ref "LED21") (pin "A") (pinfunction "A_A") (pintype "passive"))
      (node (ref "R44") (pin "1") (pinfunction "1_1") (pintype "passive"))
    )
    (net (code "50") (name "Net-(LED22-PadA)") (class "Default")
      (node (ref "LED22") (pin "A") (pinfunction "A_A") (pintype "passive"))
      (node (ref "R46") (pin "1") (pinfunction "1_1") (pintype "passive"))
    )
    (net (code "51") (name "Net-(LED23-PadA)") (class "Default")
      (node (ref "LED23") (pin "A") (pinfunction "A_A") (pintype "passive"))
      (node (ref "R48") (pin "1") (pinfunction "1_1") (pintype "passive"))
    )
    (net (code "52") (name "unconnected-(R1-E-Pad3)") (class "Default")
      (node (ref "R1") (pin "3") (pinfunction "E_3") (pintype "passive"))
    )
  )
)
